# electretAmplifier.net
KiCad netlist of a schematic drawn in EAGLE
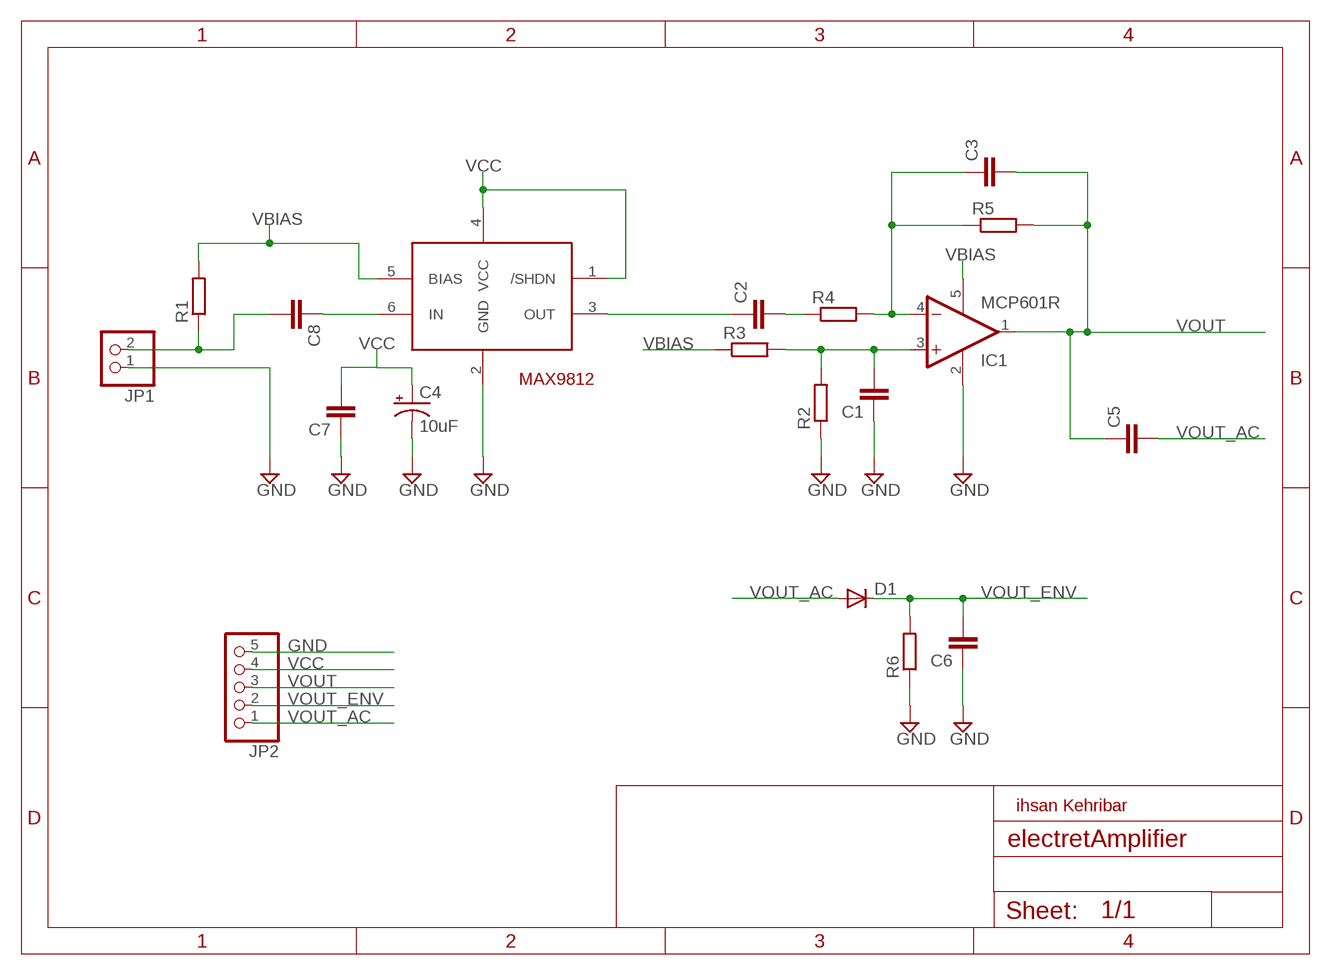
[diagram p0: schematic, sheet 1]

(export (version "E")
  (design (tool "Eeschema 10.0.6"))
  (components
    (comp (ref "C1")
      (value "C-EUC0603")
      (footprint "eagle-import:C0603")
      (libsource (lib "eagle-import") (part "C-EUC0603"))
    )
    (comp (ref "C2")
      (value "C-EUC0603")
      (footprint "eagle-import:C0603")
      (libsource (lib "eagle-import") (part "C-EUC0603"))
    )
    (comp (ref "C3")
      (value "C-EUC0603")
      (footprint "eagle-import:C0603")
      (libsource (lib "eagle-import") (part "C-EUC0603"))
    )
    (comp (ref "C4")
      (value "10uF")
      (footprint "eagle-import:EIA3216")
      (libsource (lib "eagle-import") (part "10UF-16V-10%(TANT)"))
    )
    (comp (ref "C5")
      (value "C-EUC0603")
      (footprint "eagle-import:C0603")
      (libsource (lib "eagle-import") (part "C-EUC0603"))
    )
    (comp (ref "C6")
      (value "C-EUC0603")
      (footprint "eagle-import:C0603")
      (libsource (lib "eagle-import") (part "C-EUC0603"))
    )
    (comp (ref "C7")
      (value "C-EUC0603")
      (footprint "eagle-import:C0603")
      (libsource (lib "eagle-import") (part "C-EUC0603"))
    )
    (comp (ref "C8")
      (value "C-EUC0603")
      (footprint "eagle-import:C0603")
      (libsource (lib "eagle-import") (part "C-EUC0603"))
    )
    (comp (ref "D1")
      (value "DIODESOD")
      (footprint "eagle-import:SOD-323")
      (libsource (lib "eagle-import") (part "DIODESOD"))
    )
    (comp (ref "IC1")
      (value "MCP601R")
      (footprint "eagle-import:SOT23-5")
      (libsource (lib "eagle-import") (part "MCP601R"))
    )
    (comp (ref "JP1")
      (value "HEADER-1X2ROUND")
      (footprint "eagle-import:1X02_ROUND")
      (libsource (lib "eagle-import") (part "HEADER-1X2ROUND"))
    )
    (comp (ref "JP2")
      (value "HEADER-1X5ROUND")
      (footprint "eagle-import:1X05_ROUND")
      (libsource (lib "eagle-import") (part "HEADER-1X5ROUND"))
    )
    (comp (ref "R1")
      (value "R-EU_R0603")
      (footprint "eagle-import:R0603")
      (libsource (lib "eagle-import") (part "R-EU_R0603"))
    )
    (comp (ref "R2")
      (value "R-EU_R0603")
      (footprint "eagle-import:R0603")
      (libsource (lib "eagle-import") (part "R-EU_R0603"))
    )
    (comp (ref "R3")
      (value "R-EU_R0603")
      (footprint "eagle-import:R0603")
      (libsource (lib "eagle-import") (part "R-EU_R0603"))
    )
    (comp (ref "R4")
      (value "R-EU_R0603")
      (footprint "eagle-import:R0603")
      (libsource (lib "eagle-import") (part "R-EU_R0603"))
    )
    (comp (ref "R5")
      (value "R-EU_R0603")
      (footprint "eagle-import:R0603")
      (libsource (lib "eagle-import") (part "R-EU_R0603"))
    )
    (comp (ref "R6")
      (value "R-EU_R0603")
      (footprint "eagle-import:R0603")
      (libsource (lib "eagle-import") (part "R-EU_R0603"))
    )
    (comp (ref "U$1")
      (value "IHSAN_MAX9812")
      (footprint "eagle-import:SC70-6")
      (libsource (lib "eagle-import") (part "IHSAN_MAX9812"))
    )
  )
  (nets
    (net (code "1") (name "/VBIAS") (class "Default")
      (node (ref "IC1") (pin "5") (pinfunction "V-_5") (pintype "power_in"))
      (node (ref "R1") (pin "2") (pinfunction "2_2") (pintype "passive"))
      (node (ref "R3") (pin "1") (pinfunction "1_1") (pintype "passive"))
      (node (ref "U$1") (pin "5") (pinfunction "BIAS_5") (pintype "bidirectional"))
    )
    (net (code "2") (name "/VCC") (class "Default")
      (node (ref "C4") (pin "A") (pinfunction "+_A") (pintype "passive"))
      (node (ref "C7") (pin "2") (pinfunction "2_2") (pintype "passive"))
      (node (ref "JP2") (pin "4") (pinfunction "4_4") (pintype "passive"))
      (node (ref "U$1") (pin "1") (pinfunction "/SHDN_1") (pintype "bidirectional"))
      (node (ref "U$1") (pin "4") (pinfunction "VCC_4") (pintype "bidirectional"))
    )
    (net (code "3") (name "/VOUT") (class "Default")
      (node (ref "C3") (pin "2") (pinfunction "2_2") (pintype "passive"))
      (node (ref "C5") (pin "1") (pinfunction "1_1") (pintype "passive"))
      (node (ref "IC1") (pin "1") (pinfunction "OUT_1") (pintype "output"))
      (node (ref "JP2") (pin "3") (pinfunction "3_3") (pintype "passive"))
      (node (ref "R5") (pin "2") (pinfunction "2_2") (pintype "passive"))
    )
    (net (code "4") (name "/VOUT_AC") (class "Default")
      (node (ref "C5") (pin "2") (pinfunction "2_2") (pintype "passive"))
      (node (ref "D1") (pin "2") (pinfunction "A_2") (pintype "passive"))
      (node (ref "JP2") (pin "1") (pinfunction "1_1") (pintype "passive"))
    )
    (net (code "5") (name "/VOUT_ENV") (class "Default")
      (node (ref "C6") (pin "2") (pinfunction "2_2") (pintype "passive"))
      (node (ref "D1") (pin "1") (pinfunction "C_1") (pintype "passive"))
      (node (ref "JP2") (pin "2") (pinfunction "2_2") (pintype "passive"))
      (node (ref "R6") (pin "2") (pinfunction "2_2") (pintype "passive"))
    )
    (net (code "6") (name "GND") (class "Default")
      (node (ref "C1") (pin "1") (pinfunction "1_1") (pintype "passive"))
      (node (ref "C4") (pin "C") (pinfunction "-_C") (pintype "passive"))
      (node (ref "C6") (pin "1") (pinfunction "1_1") (pintype "passive"))
      (node (ref "C7") (pin "1") (pinfunction "1_1") (pintype "passive"))
      (node (ref "IC1") (pin "2") (pinfunction "V+_2") (pintype "power_in"))
      (node (ref "JP1") (pin "1") (pinfunction "1_1") (pintype "passive"))
      (node (ref "JP2") (pin "5") (pinfunction "5_5") (pintype "passive"))
      (node (ref "R2") (pin "1") (pinfunction "1_1") (pintype "passive"))
      (node (ref "R6") (pin "1") (pinfunction "1_1") (pintype "passive"))
      (node (ref "U$1") (pin "2") (pinfunction "GND_2") (pintype "bidirectional"))
    )
    (net (code "7") (name "Net-(C2-Pad2)") (class "Default")
      (node (ref "C2") (pin "2") (pinfunction "2_2") (pintype "passive"))
      (node (ref "R4") (pin "1") (pinfunction "1_1") (pintype "passive"))
    )
    (net (code "8") (name "Net-(C8-Pad2)") (class "Default")
      (node (ref "C8") (pin "2") (pinfunction "2_2") (pintype "passive"))
      (node (ref "JP1") (pin "2") (pinfunction "2_2") (pintype "passive"))
      (node (ref "R1") (pin "1") (pinfunction "1_1") (pintype "passive"))
    )
    (net (code "9") (name "Net-(IC1-+IN)") (class "Default")
      (node (ref "C1") (pin "2") (pinfunction "2_2") (pintype "passive"))
      (node (ref "IC1") (pin "3") (pinfunction "+IN_3") (pintype "input"))
      (node (ref "R2") (pin "2") (pinfunction "2_2") (pintype "passive"))
      (node (ref "R3") (pin "2") (pinfunction "2_2") (pintype "passive"))
    )
    (net (code "10") (name "Net-(IC1--IN)") (class "Default")
      (node (ref "C3") (pin "1") (pinfunction "1_1") (pintype "passive"))
      (node (ref "IC1") (pin "4") (pinfunction "-IN_4") (pintype "input"))
      (node (ref "R4") (pin "2") (pinfunction "2_2") (pintype "passive"))
      (node (ref "R5") (pin "1") (pinfunction "1_1") (pintype "passive"))
    )
    (net (code "11") (name "Net-(U$1-IN)") (class "Default")
      (node (ref "C8") (pin "1") (pinfunction "1_1") (pintype "passive"))
      (node (ref "U$1") (pin "6") (pinfunction "IN_6") (pintype "bidirectional"))
    )
    (net (code "12") (name "Net-(U$1-OUT)") (class "Default")
      (node (ref "C2") (pin "1") (pinfunction "1_1") (pintype "passive"))
      (node (ref "U$1") (pin "3") (pinfunction "OUT_3") (pintype "bidirectional"))
    )
  )
)
